# TopLevel.net
KiCad netlist of a schematic drawn in Altium Designer
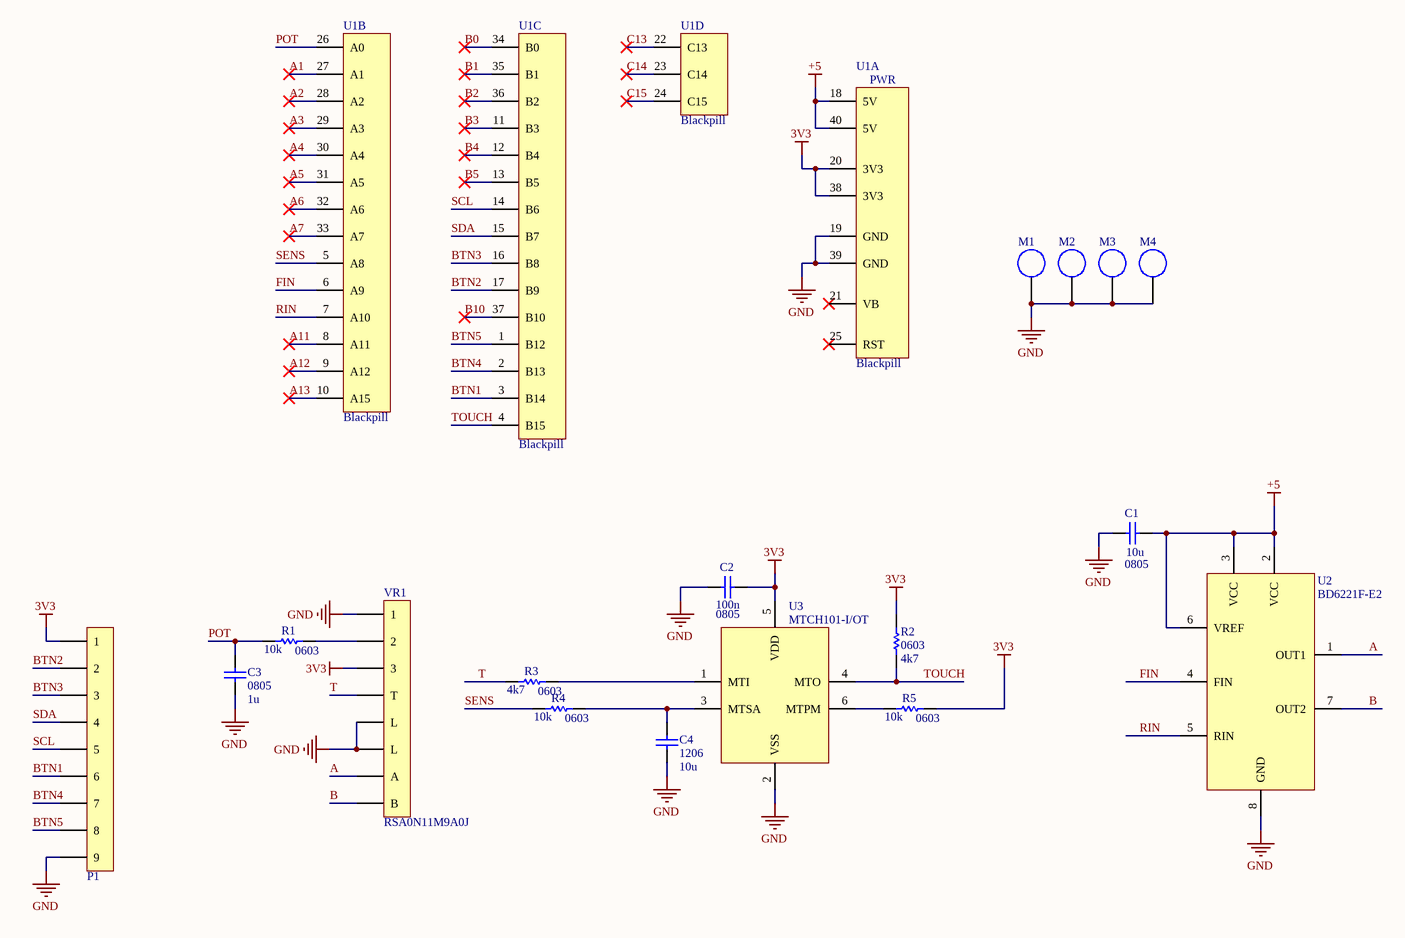
[diagram p0: TopLevel.SchDoc]

(export (version "E")
  (design (tool "Eeschema 10.0.6"))
  (components
    (comp (ref "C1")
      (value "10u")
      (footprint "CAPC2012X14N")
      (description "Generic 0805 Non Polarized Capacitor")
      (fields
        (field (name "PACKAGE") "0805")
        (field (name "MANUFACTURER") "Generic")
        (field (name "Comment") "C_NP_0805_Generic")
      )
      (libsource (lib "Altium Concord Pro on Altium 365") (part "C_NP"))
    )
    (comp (ref "C2")
      (value "100n")
      (footprint "CAPC2012X14N")
      (description "Generic 0805 Non Polarized Capacitor")
      (fields
        (field (name "PACKAGE") "0805")
        (field (name "MANUFACTURER") "Generic")
        (field (name "Comment") "C_NP_0805_Generic")
      )
      (libsource (lib "Altium Concord Pro on Altium 365") (part "C_NP"))
    )
    (comp (ref "C3")
      (value "1u")
      (footprint "CAPC2012X14N")
      (description "Generic 0805 Non Polarized Capacitor")
      (fields
        (field (name "PACKAGE") "0805")
        (field (name "MANUFACTURER") "Generic")
        (field (name "Comment") "C_NP_0805_Generic")
      )
      (libsource (lib "Altium Concord Pro on Altium 365") (part "C_NP"))
    )
    (comp (ref "C4")
      (value "10u")
      (footprint "CAPC3216X14N")
      (description "Generic 1206 Non Polarized Capacitor")
      (fields
        (field (name "PACKAGE") "1206")
        (field (name "MANUFACTURER") "Generic")
        (field (name "Comment") "C_NP_1206_Generic")
      )
      (libsource (lib "Altium Concord Pro on Altium 365") (part "C_NP"))
    )
    (comp (ref "M1")
      (value "M3 Flat Screw")
      (footprint "M3 Screw")
      (libsource (lib "OneFader") (part "M3 Flat Screw"))
    )
    (comp (ref "M2")
      (value "M3 Flat Screw")
      (footprint "M3 Screw")
      (libsource (lib "OneFader") (part "M3 Flat Screw"))
    )
    (comp (ref "M3")
      (value "M3 Flat Screw")
      (footprint "M3 Screw")
      (libsource (lib "OneFader") (part "M3 Flat Screw"))
    )
    (comp (ref "M4")
      (value "M3 Flat Screw")
      (footprint "M3 Screw")
      (libsource (lib "OneFader") (part "M3 Flat Screw"))
    )
    (comp (ref "P1") (value "9 Header") (footprint "9 Header") (libsource (lib "OneFader") (part "9 Header")))
    (comp (ref "R1")
      (value "10k")
      (footprint "RESC1608X06N")
      (description "Generic 0603 Resistor")
      (fields
        (field (name "PACKAGE") "0603")
        (field (name "MANUFACTURER") "Generic")
        (field (name "Comment") "R_0603_Generic")
      )
      (libsource (lib "Altium Concord Pro on Altium 365") (part "R"))
    )
    (comp (ref "R2")
      (value "4k7")
      (footprint "RESC1608X06N")
      (description "Generic 0603 Resistor")
      (fields
        (field (name "PACKAGE") "0603")
        (field (name "MANUFACTURER") "Generic")
        (field (name "Comment") "R_0603_Generic")
      )
      (libsource (lib "Altium Concord Pro on Altium 365") (part "R"))
    )
    (comp (ref "R3")
      (value "4k7")
      (footprint "RESC1608X06N")
      (description "Generic 0603 Resistor")
      (fields
        (field (name "PACKAGE") "0603")
        (field (name "MANUFACTURER") "Generic")
        (field (name "Comment") "R_0603_Generic")
      )
      (libsource (lib "Altium Concord Pro on Altium 365") (part "R"))
    )
    (comp (ref "R4")
      (value "10k")
      (footprint "RESC1608X06N")
      (description "Generic 0603 Resistor")
      (fields
        (field (name "PACKAGE") "0603")
        (field (name "MANUFACTURER") "Generic")
        (field (name "Comment") "R_0603_Generic")
      )
      (libsource (lib "Altium Concord Pro on Altium 365") (part "R"))
    )
    (comp (ref "R5")
      (value "10k")
      (footprint "RESC1608X06N")
      (description "Generic 0603 Resistor")
      (fields
        (field (name "PACKAGE") "0603")
        (field (name "MANUFACTURER") "Generic")
        (field (name "Comment") "R_0603_Generic")
      )
      (libsource (lib "Altium Concord Pro on Altium 365") (part "R"))
    )
    (comp (ref "U1")
      (value "Blackpill")
      (footprint "BlackPill - WeAct")
      (libsource (lib "OneFader") (part "Black Pill - We Act"))
    )
    (comp (ref "U2")
      (value "BD6221F-E2")
      (footprint "SOP127P620X160-8N")
      (description "DC Brush Motor Driver, 6 to 18 V, 1 A, -40 to 85 degC, 8-Pin SOP, RoHS, Tape and Reel")
      (fields (field (name "MANUFACTURER") "ROHM Semiconductor"))
      (libsource (lib "OneFader") (part "BD6221F-E2"))
    )
    (comp (ref "U3")
      (value "MTCH101-I/OT")
      (footprint "SOT95P270X145-6N")
      (description "Single Channel Proximity Detector 6-Pin SOT-23 T/R")
      (libsource (lib "OneFader") (part "MTCH101-I/OT"))
    )
    (comp (ref "VR1")
      (value "RSA0N11M9A0J")
      (footprint "RSA0N11M9A0J")
      (description "Motorized 10k Linear Fader")
      (libsource (lib "OneFader") (part "RSA0N11M9A0J"))
    )
  )
  (nets
    (net (code "1") (name "+5") (class "Default")
      (node (ref "C1") (pin "2") (pinfunction "2_2") (pintype "passive"))
      (node (ref "U1") (pin "18") (pinfunction "5V_18") (pintype "passive"))
      (node (ref "U1") (pin "40") (pinfunction "5V_40") (pintype "passive"))
      (node (ref "U2") (pin "2") (pinfunction "VCC_2") (pintype "power_in"))
      (node (ref "U2") (pin "3") (pinfunction "VCC_3") (pintype "power_in"))
      (node (ref "U2") (pin "6") (pinfunction "VREF_6") (pintype "passive"))
    )
    (net (code "2") (name "/A") (class "Default")
      (node (ref "U2") (pin "1") (pinfunction "OUT1_1") (pintype "tri_state"))
      (node (ref "VR1") (pin "A") (pinfunction "A_A") (pintype "passive"))
    )
    (net (code "3") (name "/A1") (class "Default")
      (node (ref "U1") (pin "27") (pinfunction "A1_27") (pintype "passive+no_connect"))
    )
    (net (code "4") (name "/A2") (class "Default")
      (node (ref "U1") (pin "28") (pinfunction "A2_28") (pintype "passive+no_connect"))
    )
    (net (code "5") (name "/A3") (class "Default")
      (node (ref "U1") (pin "29") (pinfunction "A3_29") (pintype "passive+no_connect"))
    )
    (net (code "6") (name "/A4") (class "Default")
      (node (ref "U1") (pin "30") (pinfunction "A4_30") (pintype "passive+no_connect"))
    )
    (net (code "7") (name "/A5") (class "Default")
      (node (ref "U1") (pin "31") (pinfunction "A5_31") (pintype "passive+no_connect"))
    )
    (net (code "8") (name "/A6") (class "Default")
      (node (ref "U1") (pin "32") (pinfunction "A6_32") (pintype "passive+no_connect"))
    )
    (net (code "9") (name "/A7") (class "Default")
      (node (ref "U1") (pin "33") (pinfunction "A7_33") (pintype "passive+no_connect"))
    )
    (net (code "10") (name "/A11") (class "Default")
      (node (ref "U1") (pin "8") (pinfunction "A11_8") (pintype "passive+no_connect"))
    )
    (net (code "11") (name "/A12") (class "Default")
      (node (ref "U1") (pin "9") (pinfunction "A12_9") (pintype "passive+no_connect"))
    )
    (net (code "12") (name "/A13") (class "Default")
      (node (ref "U1") (pin "10") (pinfunction "A15_10") (pintype "passive+no_connect"))
    )
    (net (code "13") (name "/B") (class "Default")
      (node (ref "U2") (pin "7") (pinfunction "OUT2_7") (pintype "tri_state"))
      (node (ref "VR1") (pin "B") (pinfunction "B_B") (pintype "passive"))
    )
    (net (code "14") (name "/B0") (class "Default")
      (node (ref "U1") (pin "34") (pinfunction "B0_34") (pintype "passive+no_connect"))
    )
    (net (code "15") (name "/B1") (class "Default")
      (node (ref "U1") (pin "35") (pinfunction "B1_35") (pintype "passive+no_connect"))
    )
    (net (code "16") (name "/B2") (class "Default")
      (node (ref "U1") (pin "36") (pinfunction "B2_36") (pintype "passive+no_connect"))
    )
    (net (code "17") (name "/B3") (class "Default")
      (node (ref "U1") (pin "11") (pinfunction "B3_11") (pintype "passive+no_connect"))
    )
    (net (code "18") (name "/B4") (class "Default")
      (node (ref "U1") (pin "12") (pinfunction "B4_12") (pintype "passive+no_connect"))
    )
    (net (code "19") (name "/B5") (class "Default")
      (node (ref "U1") (pin "13") (pinfunction "B5_13") (pintype "passive+no_connect"))
    )
    (net (code "20") (name "/B10") (class "Default")
      (node (ref "U1") (pin "37") (pinfunction "B10_37") (pintype "passive+no_connect"))
    )
    (net (code "21") (name "/BTN1") (class "Default")
      (node (ref "P1") (pin "6") (pinfunction "6_6") (pintype "passive"))
      (node (ref "U1") (pin "3") (pinfunction "B14_3") (pintype "passive"))
    )
    (net (code "22") (name "/BTN2") (class "Default")
      (node (ref "P1") (pin "2") (pinfunction "2_2") (pintype "passive"))
      (node (ref "U1") (pin "17") (pinfunction "B9_17") (pintype "passive"))
    )
    (net (code "23") (name "/BTN3") (class "Default")
      (node (ref "P1") (pin "3") (pinfunction "3_3") (pintype "passive"))
      (node (ref "U1") (pin "16") (pinfunction "B8_16") (pintype "passive"))
    )
    (net (code "24") (name "/BTN4") (class "Default")
      (node (ref "P1") (pin "7") (pinfunction "7_7") (pintype "passive"))
      (node (ref "U1") (pin "2") (pinfunction "B13_2") (pintype "passive"))
    )
    (net (code "25") (name "/BTN5") (class "Default")
      (node (ref "P1") (pin "8") (pinfunction "8_8") (pintype "passive"))
      (node (ref "U1") (pin "1") (pinfunction "B12_1") (pintype "passive"))
    )
    (net (code "26") (name "/C13") (class "Default")
      (node (ref "U1") (pin "22") (pinfunction "C13_22") (pintype "passive+no_connect"))
    )
    (net (code "27") (name "/C14") (class "Default")
      (node (ref "U1") (pin "23") (pinfunction "C14_23") (pintype "passive+no_connect"))
    )
    (net (code "28") (name "/C15") (class "Default")
      (node (ref "U1") (pin "24") (pinfunction "C15_24") (pintype "passive+no_connect"))
    )
    (net (code "29") (name "/FIN") (class "Default")
      (node (ref "U1") (pin "6") (pinfunction "A9_6") (pintype "passive"))
      (node (ref "U2") (pin "4") (pinfunction "FIN_4") (pintype "passive"))
    )
    (net (code "30") (name "/POT") (class "Default")
      (node (ref "C3") (pin "2") (pinfunction "2_2") (pintype "passive"))
      (node (ref "R1") (pin "1") (pinfunction "1_1") (pintype "passive"))
      (node (ref "U1") (pin "26") (pinfunction "A0_26") (pintype "passive"))
    )
    (net (code "31") (name "/RIN") (class "Default")
      (node (ref "U1") (pin "7") (pinfunction "A10_7") (pintype "passive"))
      (node (ref "U2") (pin "5") (pinfunction "RIN_5") (pintype "passive"))
    )
    (net (code "32") (name "/SCL") (class "Default")
      (node (ref "P1") (pin "5") (pinfunction "5_5") (pintype "passive"))
      (node (ref "U1") (pin "14") (pinfunction "B6_14") (pintype "passive"))
    )
    (net (code "33") (name "/SDA") (class "Default")
      (node (ref "P1") (pin "4") (pinfunction "4_4") (pintype "passive"))
      (node (ref "U1") (pin "15") (pinfunction "B7_15") (pintype "passive"))
    )
    (net (code "34") (name "/SENS") (class "Default")
      (node (ref "R4") (pin "1") (pinfunction "1_1") (pintype "passive"))
      (node (ref "U1") (pin "5") (pinfunction "A8_5") (pintype "passive"))
    )
    (net (code "35") (name "/T") (class "Default")
      (node (ref "R3") (pin "1") (pinfunction "1_1") (pintype "passive"))
      (node (ref "VR1") (pin "T") (pinfunction "T_T") (pintype "passive"))
    )
    (net (code "36") (name "/TOUCH") (class "Default")
      (node (ref "R2") (pin "1") (pinfunction "1_1") (pintype "passive"))
      (node (ref "U1") (pin "4") (pinfunction "B15_4") (pintype "passive"))
      (node (ref "U3") (pin "4") (pinfunction "MTO_4") (pintype "passive"))
    )
    (net (code "37") (name "3V3") (class "Default")
      (node (ref "C2") (pin "2") (pinfunction "2_2") (pintype "passive"))
      (node (ref "P1") (pin "1") (pinfunction "1_1") (pintype "passive"))
      (node (ref "R2") (pin "2") (pinfunction "2_2") (pintype "passive"))
      (node (ref "R5") (pin "2") (pinfunction "2_2") (pintype "passive"))
      (node (ref "U1") (pin "20") (pinfunction "3V3_20") (pintype "passive"))
      (node (ref "U1") (pin "38") (pinfunction "3V3_38") (pintype "passive"))
      (node (ref "U3") (pin "5") (pinfunction "VDD_5") (pintype "passive"))
      (node (ref "VR1") (pin "3") (pinfunction "3_3") (pintype "passive"))
    )
    (net (code "38") (name "GND") (class "Default")
      (node (ref "C1") (pin "1") (pinfunction "1_1") (pintype "passive"))
      (node (ref "C2") (pin "1") (pinfunction "1_1") (pintype "passive"))
      (node (ref "C3") (pin "1") (pinfunction "1_1") (pintype "passive"))
      (node (ref "C4") (pin "1") (pinfunction "1_1") (pintype "passive"))
      (node (ref "M1") (pin "1") (pinfunction "1_1") (pintype "passive"))
      (node (ref "M2") (pin "1") (pinfunction "1_1") (pintype "passive"))
      (node (ref "M3") (pin "1") (pinfunction "1_1") (pintype "passive"))
      (node (ref "M4") (pin "1") (pinfunction "1_1") (pintype "passive"))
      (node (ref "P1") (pin "9") (pinfunction "9_9") (pintype "passive"))
      (node (ref "U1") (pin "19") (pinfunction "GND_19") (pintype "passive"))
      (node (ref "U1") (pin "39") (pinfunction "GND_39") (pintype "passive"))
      (node (ref "U2") (pin "8") (pinfunction "GND_8") (pintype "power_in"))
      (node (ref "U3") (pin "2") (pinfunction "VSS_2") (pintype "passive"))
      (node (ref "VR1") (pin "1") (pinfunction "1_1") (pintype "passive"))
      (node (ref "VR1") (pin "L1") (pinfunction "L_L1") (pintype "passive"))
      (node (ref "VR1") (pin "L2") (pinfunction "L_L2") (pintype "passive"))
    )
    (net (code "39") (name "Net-(R1-Pad2)") (class "Default")
      (node (ref "R1") (pin "2") (pinfunction "2_2") (pintype "passive"))
      (node (ref "VR1") (pin "2") (pinfunction "2_2") (pintype "passive"))
    )
    (net (code "40") (name "Net-(U3-MTI)") (class "Default")
      (node (ref "R3") (pin "2") (pinfunction "2_2") (pintype "passive"))
      (node (ref "U3") (pin "1") (pinfunction "MTI_1") (pintype "passive"))
    )
    (net (code "41") (name "Net-(U3-MTPM)") (class "Default")
      (node (ref "R5") (pin "1") (pinfunction "1_1") (pintype "passive"))
      (node (ref "U3") (pin "6") (pinfunction "MTPM_6") (pintype "passive"))
    )
    (net (code "42") (name "Net-(U3-MTSA)") (class "Default")
      (node (ref "C4") (pin "2") (pinfunction "2_2") (pintype "passive"))
      (node (ref "R4") (pin "2") (pinfunction "2_2") (pintype "passive"))
      (node (ref "U3") (pin "3") (pinfunction "MTSA_3") (pintype "passive"))
    )
    (net (code "43") (name "unconnected-(U1A-RST-Pad25)") (class "Default")
      (node (ref "U1") (pin "25") (pinfunction "RST_25") (pintype "passive+no_connect"))
    )
    (net (code "44") (name "unconnected-(U1A-VB-Pad21)") (class "Default")
      (node (ref "U1") (pin "21") (pinfunction "VB_21") (pintype "passive+no_connect"))
    )
  )
)
